# Indicators.net
KiCad netlist of a schematic drawn in Altium Designer
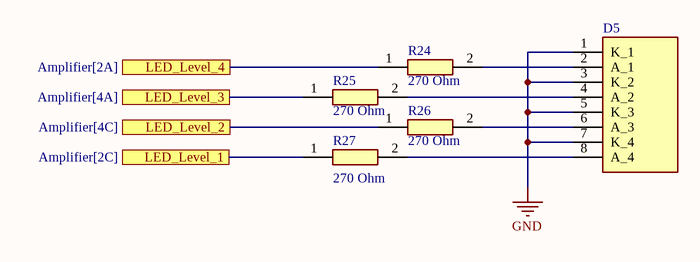
[diagram p0: Indicators.SchDoc]

(export (version "E")
  (design (tool "Eeschema 10.0.6"))
  (components
    (comp (ref "D5")
      (value "LED Bar")
      (footprint "LED_Bar")
      (description "SSB-LX2550SGW")
      (fields (field (name "MOUSER PART NUMBER") "696-SSB-LX2550SGW"))
      (libsource (lib "IR_Communication_Schematic_Lib") (part "LED Bar"))
    )
    (comp (ref "R24")
      (value "270 Ohm")
      (footprint "0805")
      (description "Resistor")
      (fields
        (field (name "MANUFACTURER_PART_NUMBER") "RP0805BRD071KL")
        (field (name "MOUSER PART NUMBER") "603-RP0805BRD071KL")
      )
      (libsource (lib "IR_Communication_Schematic_Lib") (part "Resistor"))
    )
    (comp (ref "R25")
      (value "270 Ohm")
      (footprint "0805")
      (description "Resistor")
      (fields
        (field (name "MANUFACTURER_PART_NUMBER") "RP0805BRD071KL")
        (field (name "MOUSER PART NUMBER") "603-RP0805BRD071KL")
      )
      (libsource (lib "IR_Communication_Schematic_Lib") (part "Resistor"))
    )
    (comp (ref "R26")
      (value "270 Ohm")
      (footprint "0805")
      (description "Resistor")
      (fields
        (field (name "MANUFACTURER_PART_NUMBER") "RP0805BRD071KL")
        (field (name "MOUSER PART NUMBER") "603-RP0805BRD071KL")
      )
      (libsource (lib "IR_Communication_Schematic_Lib") (part "Resistor"))
    )
    (comp (ref "R27")
      (value "270 Ohm")
      (footprint "0805")
      (description "Resistor")
      (fields
        (field (name "MANUFACTURER_PART_NUMBER") "RP0805BRD071KL")
        (field (name "MOUSER PART NUMBER") "603-RP0805BRD071KL")
      )
      (libsource (lib "IR_Communication_Schematic_Lib") (part "Resistor"))
    )
  )
  (nets
    (net (code "1") (name "/LED_Level_1") (class "Default")
      (node (ref "R27") (pin "1") (pinfunction "1_1") (pintype "passive"))
    )
    (net (code "2") (name "/LED_Level_2") (class "Default")
      (node (ref "R26") (pin "1") (pinfunction "1_1") (pintype "passive"))
    )
    (net (code "3") (name "/LED_Level_3") (class "Default")
      (node (ref "R25") (pin "1") (pinfunction "1_1") (pintype "passive"))
    )
    (net (code "4") (name "/LED_Level_4") (class "Default")
      (node (ref "R24") (pin "1") (pinfunction "1_1") (pintype "passive"))
    )
    (net (code "5") (name "GND") (class "Default")
      (node (ref "D5") (pin "1") (pinfunction "K_1_1") (pintype "passive"))
      (node (ref "D5") (pin "3") (pinfunction "K_2_3") (pintype "passive"))
      (node (ref "D5") (pin "5") (pinfunction "K_3_5") (pintype "passive"))
      (node (ref "D5") (pin "7") (pinfunction "K_4_7") (pintype "passive"))
    )
    (net (code "6") (name "Net-(D5-A_1)") (class "Default")
      (node (ref "D5") (pin "2") (pinfunction "A_1_2") (pintype "passive"))
      (node (ref "R24") (pin "2") (pinfunction "2_2") (pintype "passive"))
    )
    (net (code "7") (name "Net-(D5-A_2)") (class "Default")
      (node (ref "D5") (pin "4") (pinfunction "A_2_4") (pintype "passive"))
      (node (ref "R25") (pin "2") (pinfunction "2_2") (pintype "passive"))
    )
    (net (code "8") (name "Net-(D5-A_3)") (class "Default")
      (node (ref "D5") (pin "6") (pinfunction "A_3_6") (pintype "passive"))
      (node (ref "R26") (pin "2") (pinfunction "2_2") (pintype "passive"))
    )
    (net (code "9") (name "Net-(D5-A_4)") (class "Default")
      (node (ref "D5") (pin "8") (pinfunction "A_4_8") (pintype "passive"))
      (node (ref "R27") (pin "2") (pinfunction "2_2") (pintype "passive"))
    )
  )
)
